# led-array-12x12.net
KiCad netlist of a schematic drawn in EAGLE
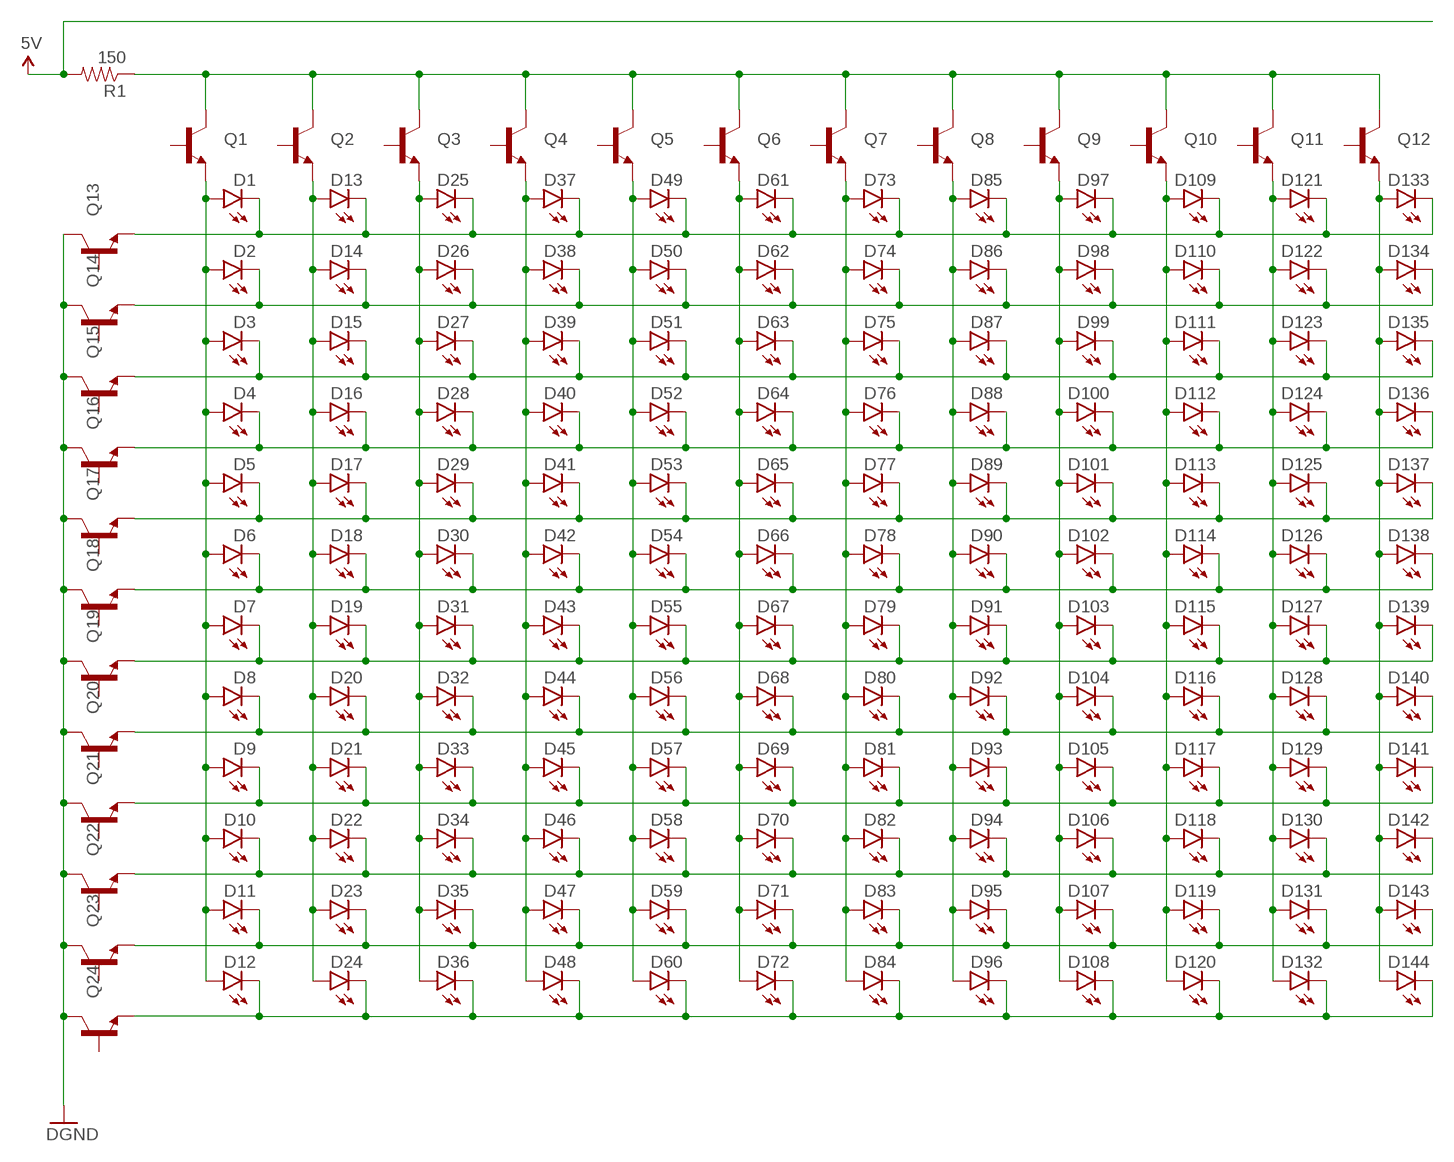
[diagram p0: schematic, sheet 1]

(export (version "E")
  (design (tool "Eeschema 10.0.6"))
  (components
    (comp (ref "D1")
      (value "LED-IR-THRUTSAL6100")
      (footprint "eagle-import:LED5MM")
      (libsource (lib "eagle-import") (part "LED-IR-THRUTSAL6100"))
    )
    (comp (ref "D2")
      (value "LED-IR-THRUTSAL6100")
      (footprint "eagle-import:LED5MM")
      (libsource (lib "eagle-import") (part "LED-IR-THRUTSAL6100"))
    )
    (comp (ref "D3")
      (value "LED-IR-THRUTSAL6100")
      (footprint "eagle-import:LED5MM")
      (libsource (lib "eagle-import") (part "LED-IR-THRUTSAL6100"))
    )
    (comp (ref "D4")
      (value "LED-IR-THRUTSAL6100")
      (footprint "eagle-import:LED5MM")
      (libsource (lib "eagle-import") (part "LED-IR-THRUTSAL6100"))
    )
    (comp (ref "D5")
      (value "LED-IR-THRUTSAL6100")
      (footprint "eagle-import:LED5MM")
      (libsource (lib "eagle-import") (part "LED-IR-THRUTSAL6100"))
    )
    (comp (ref "D6")
      (value "LED-IR-THRUTSAL6100")
      (footprint "eagle-import:LED5MM")
      (libsource (lib "eagle-import") (part "LED-IR-THRUTSAL6100"))
    )
    (comp (ref "D7")
      (value "LED-IR-THRUTSAL6100")
      (footprint "eagle-import:LED5MM")
      (libsource (lib "eagle-import") (part "LED-IR-THRUTSAL6100"))
    )
    (comp (ref "D8")
      (value "LED-IR-THRUTSAL6100")
      (footprint "eagle-import:LED5MM")
      (libsource (lib "eagle-import") (part "LED-IR-THRUTSAL6100"))
    )
    (comp (ref "D9")
      (value "LED-IR-THRUTSAL6100")
      (footprint "eagle-import:LED5MM")
      (libsource (lib "eagle-import") (part "LED-IR-THRUTSAL6100"))
    )
    (comp (ref "D10")
      (value "LED-IR-THRUTSAL6100")
      (footprint "eagle-import:LED5MM")
      (libsource (lib "eagle-import") (part "LED-IR-THRUTSAL6100"))
    )
    (comp (ref "D11")
      (value "LED-IR-THRUTSAL6100")
      (footprint "eagle-import:LED5MM")
      (libsource (lib "eagle-import") (part "LED-IR-THRUTSAL6100"))
    )
    (comp (ref "D12")
      (value "LED-IR-THRUTSAL6100")
      (footprint "eagle-import:LED5MM")
      (libsource (lib "eagle-import") (part "LED-IR-THRUTSAL6100"))
    )
    (comp (ref "D13")
      (value "LED-IR-THRUTSAL6100")
      (footprint "eagle-import:LED5MM")
      (libsource (lib "eagle-import") (part "LED-IR-THRUTSAL6100"))
    )
    (comp (ref "D14")
      (value "LED-IR-THRUTSAL6100")
      (footprint "eagle-import:LED5MM")
      (libsource (lib "eagle-import") (part "LED-IR-THRUTSAL6100"))
    )
    (comp (ref "D15")
      (value "LED-IR-THRUTSAL6100")
      (footprint "eagle-import:LED5MM")
      (libsource (lib "eagle-import") (part "LED-IR-THRUTSAL6100"))
    )
    (comp (ref "D16")
      (value "LED-IR-THRUTSAL6100")
      (footprint "eagle-import:LED5MM")
      (libsource (lib "eagle-import") (part "LED-IR-THRUTSAL6100"))
    )
    (comp (ref "D17")
      (value "LED-IR-THRUTSAL6100")
      (footprint "eagle-import:LED5MM")
      (libsource (lib "eagle-import") (part "LED-IR-THRUTSAL6100"))
    )
    (comp (ref "D18")
      (value "LED-IR-THRUTSAL6100")
      (footprint "eagle-import:LED5MM")
      (libsource (lib "eagle-import") (part "LED-IR-THRUTSAL6100"))
    )
    (comp (ref "D19")
      (value "LED-IR-THRUTSAL6100")
      (footprint "eagle-import:LED5MM")
      (libsource (lib "eagle-import") (part "LED-IR-THRUTSAL6100"))
    )
    (comp (ref "D20")
      (value "LED-IR-THRUTSAL6100")
      (footprint "eagle-import:LED5MM")
      (libsource (lib "eagle-import") (part "LED-IR-THRUTSAL6100"))
    )
    (comp (ref "D21")
      (value "LED-IR-THRUTSAL6100")
      (footprint "eagle-import:LED5MM")
      (libsource (lib "eagle-import") (part "LED-IR-THRUTSAL6100"))
    )
    (comp (ref "D22")
      (value "LED-IR-THRUTSAL6100")
      (footprint "eagle-import:LED5MM")
      (libsource (lib "eagle-import") (part "LED-IR-THRUTSAL6100"))
    )
    (comp (ref "D23")
      (value "LED-IR-THRUTSAL6100")
      (footprint "eagle-import:LED5MM")
      (libsource (lib "eagle-import") (part "LED-IR-THRUTSAL6100"))
    )
    (comp (ref "D24")
      (value "LED-IR-THRUTSAL6100")
      (footprint "eagle-import:LED5MM")
      (libsource (lib "eagle-import") (part "LED-IR-THRUTSAL6100"))
    )
    (comp (ref "D25")
      (value "LED-IR-THRUTSAL6100")
      (footprint "eagle-import:LED5MM")
      (libsource (lib "eagle-import") (part "LED-IR-THRUTSAL6100"))
    )
    (comp (ref "D26")
      (value "LED-IR-THRUTSAL6100")
      (footprint "eagle-import:LED5MM")
      (libsource (lib "eagle-import") (part "LED-IR-THRUTSAL6100"))
    )
    (comp (ref "D27")
      (value "LED-IR-THRUTSAL6100")
      (footprint "eagle-import:LED5MM")
      (libsource (lib "eagle-import") (part "LED-IR-THRUTSAL6100"))
    )
    (comp (ref "D28")
      (value "LED-IR-THRUTSAL6100")
      (footprint "eagle-import:LED5MM")
      (libsource (lib "eagle-import") (part "LED-IR-THRUTSAL6100"))
    )
    (comp (ref "D29")
      (value "LED-IR-THRUTSAL6100")
      (footprint "eagle-import:LED5MM")
      (libsource (lib "eagle-import") (part "LED-IR-THRUTSAL6100"))
    )
    (comp (ref "D30")
      (value "LED-IR-THRUTSAL6100")
      (footprint "eagle-import:LED5MM")
      (libsource (lib "eagle-import") (part "LED-IR-THRUTSAL6100"))
    )
    (comp (ref "D31")
      (value "LED-IR-THRUTSAL6100")
      (footprint "eagle-import:LED5MM")
      (libsource (lib "eagle-import") (part "LED-IR-THRUTSAL6100"))
    )
    (comp (ref "D32")
      (value "LED-IR-THRUTSAL6100")
      (footprint "eagle-import:LED5MM")
      (libsource (lib "eagle-import") (part "LED-IR-THRUTSAL6100"))
    )
    (comp (ref "D33")
      (value "LED-IR-THRUTSAL6100")
      (footprint "eagle-import:LED5MM")
      (libsource (lib "eagle-import") (part "LED-IR-THRUTSAL6100"))
    )
    (comp (ref "D34")
      (value "LED-IR-THRUTSAL6100")
      (footprint "eagle-import:LED5MM")
      (libsource (lib "eagle-import") (part "LED-IR-THRUTSAL6100"))
    )
    (comp (ref "D35")
      (value "LED-IR-THRUTSAL6100")
      (footprint "eagle-import:LED5MM")
      (libsource (lib "eagle-import") (part "LED-IR-THRUTSAL6100"))
    )
    (comp (ref "D36")
      (value "LED-IR-THRUTSAL6100")
      (footprint "eagle-import:LED5MM")
      (libsource (lib "eagle-import") (part "LED-IR-THRUTSAL6100"))
    )
    (comp (ref "D37")
      (value "LED-IR-THRUTSAL6100")
      (footprint "eagle-import:LED5MM")
      (libsource (lib "eagle-import") (part "LED-IR-THRUTSAL6100"))
    )
    (comp (ref "D38")
      (value "LED-IR-THRUTSAL6100")
      (footprint "eagle-import:LED5MM")
      (libsource (lib "eagle-import") (part "LED-IR-THRUTSAL6100"))
    )
    (comp (ref "D39")
      (value "LED-IR-THRUTSAL6100")
      (footprint "eagle-import:LED5MM")
      (libsource (lib "eagle-import") (part "LED-IR-THRUTSAL6100"))
    )
    (comp (ref "D40")
      (value "LED-IR-THRUTSAL6100")
      (footprint "eagle-import:LED5MM")
      (libsource (lib "eagle-import") (part "LED-IR-THRUTSAL6100"))
    )
    (comp (ref "D41")
      (value "LED-IR-THRUTSAL6100")
      (footprint "eagle-import:LED5MM")
      (libsource (lib "eagle-import") (part "LED-IR-THRUTSAL6100"))
    )
    (comp (ref "D42")
      (value "LED-IR-THRUTSAL6100")
      (footprint "eagle-import:LED5MM")
      (libsource (lib "eagle-import") (part "LED-IR-THRUTSAL6100"))
    )
    (comp (ref "D43")
      (value "LED-IR-THRUTSAL6100")
      (footprint "eagle-import:LED5MM")
      (libsource (lib "eagle-import") (part "LED-IR-THRUTSAL6100"))
    )
    (comp (ref "D44")
      (value "LED-IR-THRUTSAL6100")
      (footprint "eagle-import:LED5MM")
      (libsource (lib "eagle-import") (part "LED-IR-THRUTSAL6100"))
    )
    (comp (ref "D45")
      (value "LED-IR-THRUTSAL6100")
      (footprint "eagle-import:LED5MM")
      (libsource (lib "eagle-import") (part "LED-IR-THRUTSAL6100"))
    )
    (comp (ref "D46")
      (value "LED-IR-THRUTSAL6100")
      (footprint "eagle-import:LED5MM")
      (libsource (lib "eagle-import") (part "LED-IR-THRUTSAL6100"))
    )
    (comp (ref "D47")
      (value "LED-IR-THRUTSAL6100")
      (footprint "eagle-import:LED5MM")
      (libsource (lib "eagle-import") (part "LED-IR-THRUTSAL6100"))
    )
    (comp (ref "D48")
      (value "LED-IR-THRUTSAL6100")
      (footprint "eagle-import:LED5MM")
      (libsource (lib "eagle-import") (part "LED-IR-THRUTSAL6100"))
    )
    (comp (ref "D49")
      (value "LED-IR-THRUTSAL6100")
      (footprint "eagle-import:LED5MM")
      (libsource (lib "eagle-import") (part "LED-IR-THRUTSAL6100"))
    )
    (comp (ref "D50")
      (value "LED-IR-THRUTSAL6100")
      (footprint "eagle-import:LED5MM")
      (libsource (lib "eagle-import") (part "LED-IR-THRUTSAL6100"))
    )
    (comp (ref "D51")
      (value "LED-IR-THRUTSAL6100")
      (footprint "eagle-import:LED5MM")
      (libsource (lib "eagle-import") (part "LED-IR-THRUTSAL6100"))
    )
    (comp (ref "D52")
      (value "LED-IR-THRUTSAL6100")
      (footprint "eagle-import:LED5MM")
      (libsource (lib "eagle-import") (part "LED-IR-THRUTSAL6100"))
    )
    (comp (ref "D53")
      (value "LED-IR-THRUTSAL6100")
      (footprint "eagle-import:LED5MM")
      (libsource (lib "eagle-import") (part "LED-IR-THRUTSAL6100"))
    )
    (comp (ref "D54")
      (value "LED-IR-THRUTSAL6100")
      (footprint "eagle-import:LED5MM")
      (libsource (lib "eagle-import") (part "LED-IR-THRUTSAL6100"))
    )
    (comp (ref "D55")
      (value "LED-IR-THRUTSAL6100")
      (footprint "eagle-import:LED5MM")
      (libsource (lib "eagle-import") (part "LED-IR-THRUTSAL6100"))
    )
    (comp (ref "D56")
      (value "LED-IR-THRUTSAL6100")
      (footprint "eagle-import:LED5MM")
      (libsource (lib "eagle-import") (part "LED-IR-THRUTSAL6100"))
    )
    (comp (ref "D57")
      (value "LED-IR-THRUTSAL6100")
      (footprint "eagle-import:LED5MM")
      (libsource (lib "eagle-import") (part "LED-IR-THRUTSAL6100"))
    )
    (comp (ref "D58")
      (value "LED-IR-THRUTSAL6100")
      (footprint "eagle-import:LED5MM")
      (libsource (lib "eagle-import") (part "LED-IR-THRUTSAL6100"))
    )
    (comp (ref "D59")
      (value "LED-IR-THRUTSAL6100")
      (footprint "eagle-import:LED5MM")
      (libsource (lib "eagle-import") (part "LED-IR-THRUTSAL6100"))
    )
    (comp (ref "D60")
      (value "LED-IR-THRUTSAL6100")
      (footprint "eagle-import:LED5MM")
      (libsource (lib "eagle-import") (part "LED-IR-THRUTSAL6100"))
    )
    (comp (ref "D61")
      (value "LED-IR-THRUTSAL6100")
      (footprint "eagle-import:LED5MM")
      (libsource (lib "eagle-import") (part "LED-IR-THRUTSAL6100"))
    )
    (comp (ref "D62")
      (value "LED-IR-THRUTSAL6100")
      (footprint "eagle-import:LED5MM")
      (libsource (lib "eagle-import") (part "LED-IR-THRUTSAL6100"))
    )
    (comp (ref "D63")
      (value "LED-IR-THRUTSAL6100")
      (footprint "eagle-import:LED5MM")
      (libsource (lib "eagle-import") (part "LED-IR-THRUTSAL6100"))
    )
    (comp (ref "D64")
      (value "LED-IR-THRUTSAL6100")
      (footprint "eagle-import:LED5MM")
      (libsource (lib "eagle-import") (part "LED-IR-THRUTSAL6100"))
    )
    (comp (ref "D65")
      (value "LED-IR-THRUTSAL6100")
      (footprint "eagle-import:LED5MM")
      (libsource (lib "eagle-import") (part "LED-IR-THRUTSAL6100"))
    )
    (comp (ref "D66")
      (value "LED-IR-THRUTSAL6100")
      (footprint "eagle-import:LED5MM")
      (libsource (lib "eagle-import") (part "LED-IR-THRUTSAL6100"))
    )
    (comp (ref "D67")
      (value "LED-IR-THRUTSAL6100")
      (footprint "eagle-import:LED5MM")
      (libsource (lib "eagle-import") (part "LED-IR-THRUTSAL6100"))
    )
    (comp (ref "D68")
      (value "LED-IR-THRUTSAL6100")
      (footprint "eagle-import:LED5MM")
      (libsource (lib "eagle-import") (part "LED-IR-THRUTSAL6100"))
    )
    (comp (ref "D69")
      (value "LED-IR-THRUTSAL6100")
      (footprint "eagle-import:LED5MM")
      (libsource (lib "eagle-import") (part "LED-IR-THRUTSAL6100"))
    )
    (comp (ref "D70")
      (value "LED-IR-THRUTSAL6100")
      (footprint "eagle-import:LED5MM")
      (libsource (lib "eagle-import") (part "LED-IR-THRUTSAL6100"))
    )
    (comp (ref "D71")
      (value "LED-IR-THRUTSAL6100")
      (footprint "eagle-import:LED5MM")
      (libsource (lib "eagle-import") (part "LED-IR-THRUTSAL6100"))
    )
    (comp (ref "D72")
      (value "LED-IR-THRUTSAL6100")
      (footprint "eagle-import:LED5MM")
      (libsource (lib "eagle-import") (part "LED-IR-THRUTSAL6100"))
    )
    (comp (ref "D73")
      (value "LED-IR-THRUTSAL6100")
      (footprint "eagle-import:LED5MM")
      (libsource (lib "eagle-import") (part "LED-IR-THRUTSAL6100"))
    )
    (comp (ref "D74")
      (value "LED-IR-THRUTSAL6100")
      (footprint "eagle-import:LED5MM")
      (libsource (lib "eagle-import") (part "LED-IR-THRUTSAL6100"))
    )
    (comp (ref "D75")
      (value "LED-IR-THRUTSAL6100")
      (footprint "eagle-import:LED5MM")
      (libsource (lib "eagle-import") (part "LED-IR-THRUTSAL6100"))
    )
    (comp (ref "D76")
      (value "LED-IR-THRUTSAL6100")
      (footprint "eagle-import:LED5MM")
      (libsource (lib "eagle-import") (part "LED-IR-THRUTSAL6100"))
    )
    (comp (ref "D77")
      (value "LED-IR-THRUTSAL6100")
      (footprint "eagle-import:LED5MM")
      (libsource (lib "eagle-import") (part "LED-IR-THRUTSAL6100"))
    )
    (comp (ref "D78")
      (value "LED-IR-THRUTSAL6100")
      (footprint "eagle-import:LED5MM")
      (libsource (lib "eagle-import") (part "LED-IR-THRUTSAL6100"))
    )
    (comp (ref "D79")
      (value "LED-IR-THRUTSAL6100")
      (footprint "eagle-import:LED5MM")
      (libsource (lib "eagle-import") (part "LED-IR-THRUTSAL6100"))
    )
    (comp (ref "D80")
      (value "LED-IR-THRUTSAL6100")
      (footprint "eagle-import:LED5MM")
      (libsource (lib "eagle-import") (part "LED-IR-THRUTSAL6100"))
    )
    (comp (ref "D81")
      (value "LED-IR-THRUTSAL6100")
      (footprint "eagle-import:LED5MM")
      (libsource (lib "eagle-import") (part "LED-IR-THRUTSAL6100"))
    )
    (comp (ref "D82")
      (value "LED-IR-THRUTSAL6100")
      (footprint "eagle-import:LED5MM")
      (libsource (lib "eagle-import") (part "LED-IR-THRUTSAL6100"))
    )
    (comp (ref "D83")
      (value "LED-IR-THRUTSAL6100")
      (footprint "eagle-import:LED5MM")
      (libsource (lib "eagle-import") (part "LED-IR-THRUTSAL6100"))
    )
    (comp (ref "D84")
      (value "LED-IR-THRUTSAL6100")
      (footprint "eagle-import:LED5MM")
      (libsource (lib "eagle-import") (part "LED-IR-THRUTSAL6100"))
    )
    (comp (ref "D85")
      (value "LED-IR-THRUTSAL6100")
      (footprint "eagle-import:LED5MM")
      (libsource (lib "eagle-import") (part "LED-IR-THRUTSAL6100"))
    )
    (comp (ref "D86")
      (value "LED-IR-THRUTSAL6100")
      (footprint "eagle-import:LED5MM")
      (libsource (lib "eagle-import") (part "LED-IR-THRUTSAL6100"))
    )
    (comp (ref "D87")
      (value "LED-IR-THRUTSAL6100")
      (footprint "eagle-import:LED5MM")
      (libsource (lib "eagle-import") (part "LED-IR-THRUTSAL6100"))
    )
    (comp (ref "D88")
      (value "LED-IR-THRUTSAL6100")
      (footprint "eagle-import:LED5MM")
      (libsource (lib "eagle-import") (part "LED-IR-THRUTSAL6100"))
    )
    (comp (ref "D89")
      (value "LED-IR-THRUTSAL6100")
      (footprint "eagle-import:LED5MM")
      (libsource (lib "eagle-import") (part "LED-IR-THRUTSAL6100"))
    )
    (comp (ref "D90")
      (value "LED-IR-THRUTSAL6100")
      (footprint "eagle-import:LED5MM")
      (libsource (lib "eagle-import") (part "LED-IR-THRUTSAL6100"))
    )
    (comp (ref "D91")
      (value "LED-IR-THRUTSAL6100")
      (footprint "eagle-import:LED5MM")
      (libsource (lib "eagle-import") (part "LED-IR-THRUTSAL6100"))
    )
    (comp (ref "D92")
      (value "LED-IR-THRUTSAL6100")
      (footprint "eagle-import:LED5MM")
      (libsource (lib "eagle-import") (part "LED-IR-THRUTSAL6100"))
    )
    (comp (ref "D93")
      (value "LED-IR-THRUTSAL6100")
      (footprint "eagle-import:LED5MM")
      (libsource (lib "eagle-import") (part "LED-IR-THRUTSAL6100"))
    )
    (comp (ref "D94")
      (value "LED-IR-THRUTSAL6100")
      (footprint "eagle-import:LED5MM")
      (libsource (lib "eagle-import") (part "LED-IR-THRUTSAL6100"))
    )
    (comp (ref "D95")
      (value "LED-IR-THRUTSAL6100")
      (footprint "eagle-import:LED5MM")
      (libsource (lib "eagle-import") (part "LED-IR-THRUTSAL6100"))
    )
    (comp (ref "D96")
      (value "LED-IR-THRUTSAL6100")
      (footprint "eagle-import:LED5MM")
      (libsource (lib "eagle-import") (part "LED-IR-THRUTSAL6100"))
    )
    (comp (ref "D97")
      (value "LED-IR-THRUTSAL6100")
      (footprint "eagle-import:LED5MM")
      (libsource (lib "eagle-import") (part "LED-IR-THRUTSAL6100"))
    )
    (comp (ref "D98")
      (value "LED-IR-THRUTSAL6100")
      (footprint "eagle-import:LED5MM")
      (libsource (lib "eagle-import") (part "LED-IR-THRUTSAL6100"))
    )
    (comp (ref "D99")
      (value "LED-IR-THRUTSAL6100")
      (footprint "eagle-import:LED5MM")
      (libsource (lib "eagle-import") (part "LED-IR-THRUTSAL6100"))
    )
    (comp (ref "D100")
      (value "LED-IR-THRUTSAL6100")
      (footprint "eagle-import:LED5MM")
      (libsource (lib "eagle-import") (part "LED-IR-THRUTSAL6100"))
    )
    (comp (ref "D101")
      (value "LED-IR-THRUTSAL6100")
      (footprint "eagle-import:LED5MM")
      (libsource (lib "eagle-import") (part "LED-IR-THRUTSAL6100"))
    )
    (comp (ref "D102")
      (value "LED-IR-THRUTSAL6100")
      (footprint "eagle-import:LED5MM")
      (libsource (lib "eagle-import") (part "LED-IR-THRUTSAL6100"))
    )
    (comp (ref "D103")
      (value "LED-IR-THRUTSAL6100")
      (footprint "eagle-import:LED5MM")
      (libsource (lib "eagle-import") (part "LED-IR-THRUTSAL6100"))
    )
    (comp (ref "D104")
      (value "LED-IR-THRUTSAL6100")
      (footprint "eagle-import:LED5MM")
      (libsource (lib "eagle-import") (part "LED-IR-THRUTSAL6100"))
    )
    (comp (ref "D105")
      (value "LED-IR-THRUTSAL6100")
      (footprint "eagle-import:LED5MM")
      (libsource (lib "eagle-import") (part "LED-IR-THRUTSAL6100"))
    )
    (comp (ref "D106")
      (value "LED-IR-THRUTSAL6100")
      (footprint "eagle-import:LED5MM")
      (libsource (lib "eagle-import") (part "LED-IR-THRUTSAL6100"))
    )
    (comp (ref "D107")
      (value "LED-IR-THRUTSAL6100")
      (footprint "eagle-import:LED5MM")
      (libsource (lib "eagle-import") (part "LED-IR-THRUTSAL6100"))
    )
    (comp (ref "D108")
      (value "LED-IR-THRUTSAL6100")
      (footprint "eagle-import:LED5MM")
      (libsource (lib "eagle-import") (part "LED-IR-THRUTSAL6100"))
    )
    (comp (ref "D109")
      (value "LED-IR-THRUTSAL6100")
      (footprint "eagle-import:LED5MM")
      (libsource (lib "eagle-import") (part "LED-IR-THRUTSAL6100"))
    )
    (comp (ref "D110")
      (value "LED-IR-THRUTSAL6100")
      (footprint "eagle-import:LED5MM")
      (libsource (lib "eagle-import") (part "LED-IR-THRUTSAL6100"))
    )
    (comp (ref "D111")
      (value "LED-IR-THRUTSAL6100")
      (footprint "eagle-import:LED5MM")
      (libsource (lib "eagle-import") (part "LED-IR-THRUTSAL6100"))
    )
    (comp (ref "D112")
      (value "LED-IR-THRUTSAL6100")
      (footprint "eagle-import:LED5MM")
      (libsource (lib "eagle-import") (part "LED-IR-THRUTSAL6100"))
    )
    (comp (ref "D113")
      (value "LED-IR-THRUTSAL6100")
      (footprint "eagle-import:LED5MM")
      (libsource (lib "eagle-import") (part "LED-IR-THRUTSAL6100"))
    )
    (comp (ref "D114")
      (value "LED-IR-THRUTSAL6100")
      (footprint "eagle-import:LED5MM")
      (libsource (lib "eagle-import") (part "LED-IR-THRUTSAL6100"))
    )
    (comp (ref "D115")
      (value "LED-IR-THRUTSAL6100")
      (footprint "eagle-import:LED5MM")
      (libsource (lib "eagle-import") (part "LED-IR-THRUTSAL6100"))
    )
    (comp (ref "D116")
      (value "LED-IR-THRUTSAL6100")
      (footprint "eagle-import:LED5MM")
      (libsource (lib "eagle-import") (part "LED-IR-THRUTSAL6100"))
    )
    (comp (ref "D117")
      (value "LED-IR-THRUTSAL6100")
      (footprint "eagle-import:LED5MM")
      (libsource (lib "eagle-import") (part "LED-IR-THRUTSAL6100"))
    )
    (comp (ref "D118")
      (value "LED-IR-THRUTSAL6100")
      (footprint "eagle-import:LED5MM")
      (libsource (lib "eagle-import") (part "LED-IR-THRUTSAL6100"))
    )
    (comp (ref "D119")
      (value "LED-IR-THRUTSAL6100")
      (footprint "eagle-import:LED5MM")
      (libsource (lib "eagle-import") (part "LED-IR-THRUTSAL6100"))
    )
    (comp (ref "D120")
      (value "LED-IR-THRUTSAL6100")
      (footprint "eagle-import:LED5MM")
      (libsource (lib "eagle-import") (part "LED-IR-THRUTSAL6100"))
    )
    (comp (ref "D121")
      (value "LED-IR-THRUTSAL6100")
      (footprint "eagle-import:LED5MM")
      (libsource (lib "eagle-import") (part "LED-IR-THRUTSAL6100"))
    )
    (comp (ref "D122")
      (value "LED-IR-THRUTSAL6100")
      (footprint "eagle-import:LED5MM")
      (libsource (lib "eagle-import") (part "LED-IR-THRUTSAL6100"))
    )
    (comp (ref "D123")
      (value "LED-IR-THRUTSAL6100")
      (footprint "eagle-import:LED5MM")
      (libsource (lib "eagle-import") (part "LED-IR-THRUTSAL6100"))
    )
    (comp (ref "D124")
      (value "LED-IR-THRUTSAL6100")
      (footprint "eagle-import:LED5MM")
      (libsource (lib "eagle-import") (part "LED-IR-THRUTSAL6100"))
    )
    (comp (ref "D125")
      (value "LED-IR-THRUTSAL6100")
      (footprint "eagle-import:LED5MM")
      (libsource (lib "eagle-import") (part "LED-IR-THRUTSAL6100"))
    )
    (comp (ref "D126")
      (value "LED-IR-THRUTSAL6100")
      (footprint "eagle-import:LED5MM")
      (libsource (lib "eagle-import") (part "LED-IR-THRUTSAL6100"))
    )
    (comp (ref "D127")
      (value "LED-IR-THRUTSAL6100")
      (footprint "eagle-import:LED5MM")
      (libsource (lib "eagle-import") (part "LED-IR-THRUTSAL6100"))
    )
    (comp (ref "D128")
      (value "LED-IR-THRUTSAL6100")
      (footprint "eagle-import:LED5MM")
      (libsource (lib "eagle-import") (part "LED-IR-THRUTSAL6100"))
    )
    (comp (ref "D129")
      (value "LED-IR-THRUTSAL6100")
      (footprint "eagle-import:LED5MM")
      (libsource (lib "eagle-import") (part "LED-IR-THRUTSAL6100"))
    )
    (comp (ref "D130")
      (value "LED-IR-THRUTSAL6100")
      (footprint "eagle-import:LED5MM")
      (libsource (lib "eagle-import") (part "LED-IR-THRUTSAL6100"))
    )
    (comp (ref "D131")
      (value "LED-IR-THRUTSAL6100")
      (footprint "eagle-import:LED5MM")
      (libsource (lib "eagle-import") (part "LED-IR-THRUTSAL6100"))
    )
    (comp (ref "D132")
      (value "LED-IR-THRUTSAL6100")
      (footprint "eagle-import:LED5MM")
      (libsource (lib "eagle-import") (part "LED-IR-THRUTSAL6100"))
    )
    (comp (ref "D133")
      (value "LED-IR-THRUTSAL6100")
      (footprint "eagle-import:LED5MM")
      (libsource (lib "eagle-import") (part "LED-IR-THRUTSAL6100"))
    )
    (comp (ref "D134")
      (value "LED-IR-THRUTSAL6100")
      (footprint "eagle-import:LED5MM")
      (libsource (lib "eagle-import") (part "LED-IR-THRUTSAL6100"))
    )
    (comp (ref "D135")
      (value "LED-IR-THRUTSAL6100")
      (footprint "eagle-import:LED5MM")
      (libsource (lib "eagle-import") (part "LED-IR-THRUTSAL6100"))
    )
    (comp (ref "D136")
      (value "LED-IR-THRUTSAL6100")
      (footprint "eagle-import:LED5MM")
      (libsource (lib "eagle-import") (part "LED-IR-THRUTSAL6100"))
    )
    (comp (ref "D137")
      (value "LED-IR-THRUTSAL6100")
      (footprint "eagle-import:LED5MM")
      (libsource (lib "eagle-import") (part "LED-IR-THRUTSAL6100"))
    )
    (comp (ref "D138")
      (value "LED-IR-THRUTSAL6100")
      (footprint "eagle-import:LED5MM")
      (libsource (lib "eagle-import") (part "LED-IR-THRUTSAL6100"))
    )
    (comp (ref "D139")
      (value "LED-IR-THRUTSAL6100")
      (footprint "eagle-import:LED5MM")
      (libsource (lib "eagle-import") (part "LED-IR-THRUTSAL6100"))
    )
    (comp (ref "D140")
      (value "LED-IR-THRUTSAL6100")
      (footprint "eagle-import:LED5MM")
      (libsource (lib "eagle-import") (part "LED-IR-THRUTSAL6100"))
    )
    (comp (ref "D141")
      (value "LED-IR-THRUTSAL6100")
      (footprint "eagle-import:LED5MM")
      (libsource (lib "eagle-import") (part "LED-IR-THRUTSAL6100"))
    )
    (comp (ref "D142")
      (value "LED-IR-THRUTSAL6100")
      (footprint "eagle-import:LED5MM")
      (libsource (lib "eagle-import") (part "LED-IR-THRUTSAL6100"))
    )
    (comp (ref "D143")
      (value "LED-IR-THRUTSAL6100")
      (footprint "eagle-import:LED5MM")
      (libsource (lib "eagle-import") (part "LED-IR-THRUTSAL6100"))
    )
    (comp (ref "D144")
      (value "LED-IR-THRUTSAL6100")
      (footprint "eagle-import:LED5MM")
      (libsource (lib "eagle-import") (part "LED-IR-THRUTSAL6100"))
    )
    (comp (ref "Q1")
      (value "TRANSISTOR_NPNMMBT2222A")
      (footprint "eagle-import:SOT23-3")
      (libsource (lib "eagle-import") (part "TRANSISTOR_NPNMMBT2222A"))
    )
    (comp (ref "Q2")
      (value "TRANSISTOR_NPNMMBT2222A")
      (footprint "eagle-import:SOT23-3")
      (libsource (lib "eagle-import") (part "TRANSISTOR_NPNMMBT2222A"))
    )
    (comp (ref "Q3")
      (value "TRANSISTOR_NPNMMBT2222A")
      (footprint "eagle-import:SOT23-3")
      (libsource (lib "eagle-import") (part "TRANSISTOR_NPNMMBT2222A"))
    )
    (comp (ref "Q4")
      (value "TRANSISTOR_NPNMMBT2222A")
      (footprint "eagle-import:SOT23-3")
      (libsource (lib "eagle-import") (part "TRANSISTOR_NPNMMBT2222A"))
    )
    (comp (ref "Q5")
      (value "TRANSISTOR_NPNMMBT2222A")
      (footprint "eagle-import:SOT23-3")
      (libsource (lib "eagle-import") (part "TRANSISTOR_NPNMMBT2222A"))
    )
    (comp (ref "Q6")
      (value "TRANSISTOR_NPNMMBT2222A")
      (footprint "eagle-import:SOT23-3")
      (libsource (lib "eagle-import") (part "TRANSISTOR_NPNMMBT2222A"))
    )
    (comp (ref "Q7")
      (value "TRANSISTOR_NPNMMBT2222A")
      (footprint "eagle-import:SOT23-3")
      (libsource (lib "eagle-import") (part "TRANSISTOR_NPNMMBT2222A"))
    )
    (comp (ref "Q8")
      (value "TRANSISTOR_NPNMMBT2222A")
      (footprint "eagle-import:SOT23-3")
      (libsource (lib "eagle-import") (part "TRANSISTOR_NPNMMBT2222A"))
    )
    (comp (ref "Q9")
      (value "TRANSISTOR_NPNMMBT2222A")
      (footprint "eagle-import:SOT23-3")
      (libsource (lib "eagle-import") (part "TRANSISTOR_NPNMMBT2222A"))
    )
    (comp (ref "Q10")
      (value "TRANSISTOR_NPNMMBT2222A")
      (footprint "eagle-import:SOT23-3")
      (libsource (lib "eagle-import") (part "TRANSISTOR_NPNMMBT2222A"))
    )
    (comp (ref "Q11")
      (value "TRANSISTOR_NPNMMBT2222A")
      (footprint "eagle-import:SOT23-3")
      (libsource (lib "eagle-import") (part "TRANSISTOR_NPNMMBT2222A"))
    )
    (comp (ref "Q12")
      (value "TRANSISTOR_NPNMMBT2222A")
      (footprint "eagle-import:SOT23-3")
      (libsource (lib "eagle-import") (part "TRANSISTOR_NPNMMBT2222A"))
    )
    (comp (ref "Q13")
      (value "TRANSISTOR_NPNMMBT2222A")
      (footprint "eagle-import:SOT23-3")
      (libsource (lib "eagle-import") (part "TRANSISTOR_NPNMMBT2222A"))
    )
    (comp (ref "Q14")
      (value "TRANSISTOR_NPNMMBT2222A")
      (footprint "eagle-import:SOT23-3")
      (libsource (lib "eagle-import") (part "TRANSISTOR_NPNMMBT2222A"))
    )
    (comp (ref "Q15")
      (value "TRANSISTOR_NPNMMBT2222A")
      (footprint "eagle-import:SOT23-3")
      (libsource (lib "eagle-import") (part "TRANSISTOR_NPNMMBT2222A"))
    )
    (comp (ref "Q16")
      (value "TRANSISTOR_NPNMMBT2222A")
      (footprint "eagle-import:SOT23-3")
      (libsource (lib "eagle-import") (part "TRANSISTOR_NPNMMBT2222A"))
    )
    (comp (ref "Q17")
      (value "TRANSISTOR_NPNMMBT2222A")
      (footprint "eagle-import:SOT23-3")
      (libsource (lib "eagle-import") (part "TRANSISTOR_NPNMMBT2222A"))
    )
    (comp (ref "Q18")
      (value "TRANSISTOR_NPNMMBT2222A")
      (footprint "eagle-import:SOT23-3")
      (libsource (lib "eagle-import") (part "TRANSISTOR_NPNMMBT2222A"))
    )
    (comp (ref "Q19")
      (value "TRANSISTOR_NPNMMBT2222A")
      (footprint "eagle-import:SOT23-3")
      (libsource (lib "eagle-import") (part "TRANSISTOR_NPNMMBT2222A"))
    )
    (comp (ref "Q20")
      (value "TRANSISTOR_NPNMMBT2222A")
      (footprint "eagle-import:SOT23-3")
      (libsource (lib "eagle-import") (part "TRANSISTOR_NPNMMBT2222A"))
    )
    (comp (ref "Q21")
      (value "TRANSISTOR_NPNMMBT2222A")
      (footprint "eagle-import:SOT23-3")
      (libsource (lib "eagle-import") (part "TRANSISTOR_NPNMMBT2222A"))
    )
    (comp (ref "Q22")
      (value "TRANSISTOR_NPNMMBT2222A")
      (footprint "eagle-import:SOT23-3")
      (libsource (lib "eagle-import") (part "TRANSISTOR_NPNMMBT2222A"))
    )
    (comp (ref "Q23")
      (value "TRANSISTOR_NPNMMBT2222A")
      (footprint "eagle-import:SOT23-3")
      (libsource (lib "eagle-import") (part "TRANSISTOR_NPNMMBT2222A"))
    )
    (comp (ref "Q24")
      (value "TRANSISTOR_NPNMMBT2222A")
      (footprint "eagle-import:SOT23-3")
      (libsource (lib "eagle-import") (part "TRANSISTOR_NPNMMBT2222A"))
    )
    (comp (ref "R1")
      (value "150")
      (footprint "eagle-import:0805")
      (libsource (lib "eagle-import") (part "RESISTOR0805-RES"))
    )
  )
  (nets
    (net (code "1") (name "5V") (class "Default")
      (node (ref "R1") (pin "2") (pinfunction "2_2") (pintype "passive"))
    )
    (net (code "2") (name "DGND") (class "Default")
      (node (ref "Q13") (pin "3") (pinfunction "C_3") (pintype "passive"))
      (node (ref "Q14") (pin "3") (pinfunction "C_3") (pintype "passive"))
      (node (ref "Q15") (pin "3") (pinfunction "C_3") (pintype "passive"))
      (node (ref "Q16") (pin "3") (pinfunction "C_3") (pintype "passive"))
      (node (ref "Q17") (pin "3") (pinfunction "C_3") (pintype "passive"))
      (node (ref "Q18") (pin "3") (pinfunction "C_3") (pintype "passive"))
      (node (ref "Q19") (pin "3") (pinfunction "C_3") (pintype "passive"))
      (node (ref "Q20") (pin "3") (pinfunction "C_3") (pintype "passive"))
      (node (ref "Q21") (pin "3") (pinfunction "C_3") (pintype "passive"))
      (node (ref "Q22") (pin "3") (pinfunction "C_3") (pintype "passive"))
      (node (ref "Q23") (pin "3") (pinfunction "C_3") (pintype "passive"))
      (node (ref "Q24") (pin "3") (pinfunction "C_3") (pintype "passive"))
    )
    (net (code "3") (name "Net-(D1-C)") (class "Default")
      (node (ref "D1") (pin "K") (pinfunction "C_K") (pintype "passive"))
      (node (ref "D109") (pin "K") (pinfunction "C_K") (pintype "passive"))
      (node (ref "D121") (pin "K") (pinfunction "C_K") (pintype "passive"))
      (node (ref "D13") (pin "K") (pinfunction "C_K") (pintype "passive"))
      (node (ref "D133") (pin "K") (pinfunction "C_K") (pintype "passive"))
      (node (ref "D25") (pin "K") (pinfunction "C_K") (pintype "passive"))
      (node (ref "D37") (pin "K") (pinfunction "C_K") (pintype "passive"))
      (node (ref "D49") (pin "K") (pinfunction "C_K") (pintype "passive"))
      (node (ref "D61") (pin "K") (pinfunction "C_K") (pintype "passive"))
      (node (ref "D73") (pin "K") (pinfunction "C_K") (pintype "passive"))
      (node (ref "D85") (pin "K") (pinfunction "C_K") (pintype "passive"))
      (node (ref "D97") (pin "K") (pinfunction "C_K") (pintype "passive"))
      (node (ref "Q13") (pin "2") (pinfunction "E_2") (pintype "passive"))
    )
    (net (code "4") (name "Net-(D10-C)") (class "Default")
      (node (ref "D10") (pin "K") (pinfunction "C_K") (pintype "passive"))
      (node (ref "D106") (pin "K") (pinfunction "C_K") (pintype "passive"))
      (node (ref "D118") (pin "K") (pinfunction "C_K") (pintype "passive"))
      (node (ref "D130") (pin "K") (pinfunction "C_K") (pintype "passive"))
      (node (ref "D142") (pin "K") (pinfunction "C_K") (pintype "passive"))
      (node (ref "D22") (pin "K") (pinfunction "C_K") (pintype "passive"))
      (node (ref "D34") (pin "K") (pinfunction "C_K") (pintype "passive"))
      (node (ref "D46") (pin "K") (pinfunction "C_K") (pintype "passive"))
      (node (ref "D58") (pin "K") (pinfunction "C_K") (pintype "passive"))
      (node (ref "D70") (pin "K") (pinfunction "C_K") (pintype "passive"))
      (node (ref "D82") (pin "K") (pinfunction "C_K") (pintype "passive"))
      (node (ref "D94") (pin "K") (pinfunction "C_K") (pintype "passive"))
      (node (ref "Q22") (pin "2") (pinfunction "E_2") (pintype "passive"))
    )
    (net (code "5") (name "Net-(D100-C)") (class "Default")
      (node (ref "D100") (pin "K") (pinfunction "C_K") (pintype "passive"))
      (node (ref "D112") (pin "K") (pinfunction "C_K") (pintype "passive"))
      (node (ref "D124") (pin "K") (pinfunction "C_K") (pintype "passive"))
      (node (ref "D136") (pin "K") (pinfunction "C_K") (pintype "passive"))
      (node (ref "D16") (pin "K") (pinfunction "C_K") (pintype "passive"))
      (node (ref "D28") (pin "K") (pinfunction "C_K") (pintype "passive"))
      (node (ref "D4") (pin "K") (pinfunction "C_K") (pintype "passive"))
      (node (ref "D40") (pin "K") (pinfunction "C_K") (pintype "passive"))
      (node (ref "D52") (pin "K") (pinfunction "C_K") (pintype "passive"))
      (node (ref "D64") (pin "K") (pinfunction "C_K") (pintype "passive"))
      (node (ref "D76") (pin "K") (pinfunction "C_K") (pintype "passive"))
      (node (ref "D88") (pin "K") (pinfunction "C_K") (pintype "passive"))
      (node (ref "Q16") (pin "2") (pinfunction "E_2") (pintype "passive"))
    )
    (net (code "6") (name "Net-(D101-C)") (class "Default")
      (node (ref "D101") (pin "K") (pinfunction "C_K") (pintype "passive"))
      (node (ref "D113") (pin "K") (pinfunction "C_K") (pintype "passive"))
      (node (ref "D125") (pin "K") (pinfunction "C_K") (pintype "passive"))
      (node (ref "D137") (pin "K") (pinfunction "C_K") (pintype "passive"))
      (node (ref "D17") (pin "K") (pinfunction "C_K") (pintype "passive"))
      (node (ref "D29") (pin "K") (pinfunction "C_K") (pintype "passive"))
      (node (ref "D41") (pin "K") (pinfunction "C_K") (pintype "passive"))
      (node (ref "D5") (pin "K") (pinfunction "C_K") (pintype "passive"))
      (node (ref "D53") (pin "K") (pinfunction "C_K") (pintype "passive"))
      (node (ref "D65") (pin "K") (pinfunction "C_K") (pintype "passive"))
      (node (ref "D77") (pin "K") (pinfunction "C_K") (pintype "passive"))
      (node (ref "D89") (pin "K") (pinfunction "C_K") (pintype "passive"))
      (node (ref "Q17") (pin "2") (pinfunction "E_2") (pintype "passive"))
    )
    (net (code "7") (name "Net-(D102-C)") (class "Default")
      (node (ref "D102") (pin "K") (pinfunction "C_K") (pintype "passive"))
      (node (ref "D114") (pin "K") (pinfunction "C_K") (pintype "passive"))
      (node (ref "D126") (pin "K") (pinfunction "C_K") (pintype "passive"))
      (node (ref "D138") (pin "K") (pinfunction "C_K") (pintype "passive"))
      (node (ref "D18") (pin "K") (pinfunction "C_K") (pintype "passive"))
      (node (ref "D30") (pin "K") (pinfunction "C_K") (pintype "passive"))
      (node (ref "D42") (pin "K") (pinfunction "C_K") (pintype "passive"))
      (node (ref "D54") (pin "K") (pinfunction "C_K") (pintype "passive"))
      (node (ref "D6") (pin "K") (pinfunction "C_K") (pintype "passive"))
      (node (ref "D66") (pin "K") (pinfunction "C_K") (pintype "passive"))
      (node (ref "D78") (pin "K") (pinfunction "C_K") (pintype "passive"))
      (node (ref "D90") (pin "K") (pinfunction "C_K") (pintype "passive"))
      (node (ref "Q18") (pin "2") (pinfunction "E_2") (pintype "passive"))
    )
    (net (code "8") (name "Net-(D103-C)") (class "Default")
      (node (ref "D103") (pin "K") (pinfunction "C_K") (pintype "passive"))
      (node (ref "D115") (pin "K") (pinfunction "C_K") (pintype "passive"))
      (node (ref "D127") (pin "K") (pinfunction "C_K") (pintype "passive"))
      (node (ref "D139") (pin "K") (pinfunction "C_K") (pintype "passive"))
      (node (ref "D19") (pin "K") (pinfunction "C_K") (pintype "passive"))
      (node (ref "D31") (pin "K") (pinfunction "C_K") (pintype "passive"))
      (node (ref "D43") (pin "K") (pinfunction "C_K") (pintype "passive"))
      (node (ref "D55") (pin "K") (pinfunction "C_K") (pintype "passive"))
      (node (ref "D67") (pin "K") (pinfunction "C_K") (pintype "passive"))
      (node (ref "D7") (pin "K") (pinfunction "C_K") (pintype "passive"))
      (node (ref "D79") (pin "K") (pinfunction "C_K") (pintype "passive"))
      (node (ref "D91") (pin "K") (pinfunction "C_K") (pintype "passive"))
      (node (ref "Q19") (pin "2") (pinfunction "E_2") (pintype "passive"))
    )
    (net (code "9") (name "Net-(D104-C)") (class "Default")
      (node (ref "D104") (pin "K") (pinfunction "C_K") (pintype "passive"))
      (node (ref "D116") (pin "K") (pinfunction "C_K") (pintype "passive"))
      (node (ref "D128") (pin "K") (pinfunction "C_K") (pintype "passive"))
      (node (ref "D140") (pin "K") (pinfunction "C_K") (pintype "passive"))
      (node (ref "D20") (pin "K") (pinfunction "C_K") (pintype "passive"))
      (node (ref "D32") (pin "K") (pinfunction "C_K") (pintype "passive"))
      (node (ref "D44") (pin "K") (pinfunction "C_K") (pintype "passive"))
      (node (ref "D56") (pin "K") (pinfunction "C_K") (pintype "passive"))
      (node (ref "D68") (pin "K") (pinfunction "C_K") (pintype "passive"))
      (node (ref "D8") (pin "K") (pinfunction "C_K") (pintype "passive"))
      (node (ref "D80") (pin "K") (pinfunction "C_K") (pintype "passive"))
      (node (ref "D92") (pin "K") (pinfunction "C_K") (pintype "passive"))
      (node (ref "Q20") (pin "2") (pinfunction "E_2") (pintype "passive"))
    )
    (net (code "10") (name "Net-(D105-C)") (class "Default")
      (node (ref "D105") (pin "K") (pinfunction "C_K") (pintype "passive"))
      (node (ref "D117") (pin "K") (pinfunction "C_K") (pintype "passive"))
      (node (ref "D129") (pin "K") (pinfunction "C_K") (pintype "passive"))
      (node (ref "D141") (pin "K") (pinfunction "C_K") (pintype "passive"))
      (node (ref "D21") (pin "K") (pinfunction "C_K") (pintype "passive"))
      (node (ref "D33") (pin "K") (pinfunction "C_K") (pintype "passive"))
      (node (ref "D45") (pin "K") (pinfunction "C_K") (pintype "passive"))
      (node (ref "D57") (pin "K") (pinfunction "C_K") (pintype "passive"))
      (node (ref "D69") (pin "K") (pinfunction "C_K") (pintype "passive"))
      (node (ref "D81") (pin "K") (pinfunction "C_K") (pintype "passive"))
      (node (ref "D9") (pin "K") (pinfunction "C_K") (pintype "passive"))
      (node (ref "D93") (pin "K") (pinfunction "C_K") (pintype "passive"))
      (node (ref "Q21") (pin "2") (pinfunction "E_2") (pintype "passive"))
    )
    (net (code "11") (name "Net-(D107-C)") (class "Default")
      (node (ref "D107") (pin "K") (pinfunction "C_K") (pintype "passive"))
      (node (ref "D11") (pin "K") (pinfunction "C_K") (pintype "passive"))
      (node (ref "D119") (pin "K") (pinfunction "C_K") (pintype "passive"))
      (node (ref "D131") (pin "K") (pinfunction "C_K") (pintype "passive"))
      (node (ref "D143") (pin "K") (pinfunction "C_K") (pintype "passive"))
      (node (ref "D23") (pin "K") (pinfunction "C_K") (pintype "passive"))
      (node (ref "D35") (pin "K") (pinfunction "C_K") (pintype "passive"))
      (node (ref "D47") (pin "K") (pinfunction "C_K") (pintype "passive"))
      (node (ref "D59") (pin "K") (pinfunction "C_K") (pintype "passive"))
      (node (ref "D71") (pin "K") (pinfunction "C_K") (pintype "passive"))
      (node (ref "D83") (pin "K") (pinfunction "C_K") (pintype "passive"))
      (node (ref "D95") (pin "K") (pinfunction "C_K") (pintype "passive"))
      (node (ref "Q23") (pin "2") (pinfunction "E_2") (pintype "passive"))
    )
    (net (code "12") (name "Net-(D108-C)") (class "Default")
      (node (ref "D108") (pin "K") (pinfunction "C_K") (pintype "passive"))
      (node (ref "D12") (pin "K") (pinfunction "C_K") (pintype "passive"))
      (node (ref "D120") (pin "K") (pinfunction "C_K") (pintype "passive"))
      (node (ref "D132") (pin "K") (pinfunction "C_K") (pintype "passive"))
      (node (ref "D144") (pin "K") (pinfunction "C_K") (pintype "passive"))
      (node (ref "D24") (pin "K") (pinfunction "C_K") (pintype "passive"))
      (node (ref "D36") (pin "K") (pinfunction "C_K") (pintype "passive"))
      (node (ref "D48") (pin "K") (pinfunction "C_K") (pintype "passive"))
      (node (ref "D60") (pin "K") (pinfunction "C_K") (pintype "passive"))
      (node (ref "D72") (pin "K") (pinfunction "C_K") (pintype "passive"))
      (node (ref "D84") (pin "K") (pinfunction "C_K") (pintype "passive"))
      (node (ref "D96") (pin "K") (pinfunction "C_K") (pintype "passive"))
      (node (ref "Q24") (pin "2") (pinfunction "E_2") (pintype "passive"))
    )
    (net (code "13") (name "Net-(D110-C)") (class "Default")
      (node (ref "D110") (pin "K") (pinfunction "C_K") (pintype "passive"))
      (node (ref "D122") (pin "K") (pinfunction "C_K") (pintype "passive"))
      (node (ref "D134") (pin "K") (pinfunction "C_K") (pintype "passive"))
      (node (ref "D14") (pin "K") (pinfunction "C_K") (pintype "passive"))
      (node (ref "D2") (pin "K") (pinfunction "C_K") (pintype "passive"))
      (node (ref "D26") (pin "K") (pinfunction "C_K") (pintype "passive"))
      (node (ref "D38") (pin "K") (pinfunction "C_K") (pintype "passive"))
      (node (ref "D50") (pin "K") (pinfunction "C_K") (pintype "passive"))
      (node (ref "D62") (pin "K") (pinfunction "C_K") (pintype "passive"))
      (node (ref "D74") (pin "K") (pinfunction "C_K") (pintype "passive"))
      (node (ref "D86") (pin "K") (pinfunction "C_K") (pintype "passive"))
      (node (ref "D98") (pin "K") (pinfunction "C_K") (pintype "passive"))
      (node (ref "Q14") (pin "2") (pinfunction "E_2") (pintype "passive"))
    )
    (net (code "14") (name "Net-(D111-C)") (class "Default")
      (node (ref "D111") (pin "K") (pinfunction "C_K") (pintype "passive"))
      (node (ref "D123") (pin "K") (pinfunction "C_K") (pintype "passive"))
      (node (ref "D135") (pin "K") (pinfunction "C_K") (pintype "passive"))
      (node (ref "D15") (pin "K") (pinfunction "C_K") (pintype "passive"))
      (node (ref "D27") (pin "K") (pinfunction "C_K") (pintype "passive"))
      (node (ref "D3") (pin "K") (pinfunction "C_K") (pintype "passive"))
      (node (ref "D39") (pin "K") (pinfunction "C_K") (pintype "passive"))
      (node (ref "D51") (pin "K") (pinfunction "C_K") (pintype "passive"))
      (node (ref "D63") (pin "K") (pinfunction "C_K") (pintype "passive"))
      (node (ref "D75") (pin "K") (pinfunction "C_K") (pintype "passive"))
      (node (ref "D87") (pin "K") (pinfunction "C_K") (pintype "passive"))
      (node (ref "D99") (pin "K") (pinfunction "C_K") (pintype "passive"))
      (node (ref "Q15") (pin "2") (pinfunction "E_2") (pintype "passive"))
    )
    (net (code "15") (name "Net-(Q1-C)") (class "Default")
      (node (ref "Q1") (pin "3") (pinfunction "C_3") (pintype "passive"))
      (node (ref "Q10") (pin "3") (pinfunction "C_3") (pintype "passive"))
      (node (ref "Q11") (pin "3") (pinfunction "C_3") (pintype "passive"))
      (node (ref "Q12") (pin "3") (pinfunction "C_3") (pintype "passive"))
      (node (ref "Q2") (pin "3") (pinfunction "C_3") (pintype "passive"))
      (node (ref "Q3") (pin "3") (pinfunction "C_3") (pintype "passive"))
      (node (ref "Q4") (pin "3") (pinfunction "C_3") (pintype "passive"))
      (node (ref "Q5") (pin "3") (pinfunction "C_3") (pintype "passive"))
      (node (ref "Q6") (pin "3") (pinfunction "C_3") (pintype "passive"))
      (node (ref "Q7") (pin "3") (pinfunction "C_3") (pintype "passive"))
      (node (ref "Q8") (pin "3") (pinfunction "C_3") (pintype "passive"))
      (node (ref "Q9") (pin "3") (pinfunction "C_3") (pintype "passive"))
      (node (ref "R1") (pin "1") (pinfunction "1_1") (pintype "passive"))
    )
    (net (code "16") (name "Net-(Q1-E)") (class "Default")
      (node (ref "D1") (pin "A") (pinfunction "A_A") (pintype "passive"))
      (node (ref "D10") (pin "A") (pinfunction "A_A") (pintype "passive"))
      (node (ref "D11") (pin "A") (pinfunction "A_A") (pintype "passive"))
      (node (ref "D12") (pin "A") (pinfunction "A_A") (pintype "passive"))
      (node (ref "D2") (pin "A") (pinfunction "A_A") (pintype "passive"))
      (node (ref "D3") (pin "A") (pinfunction "A_A") (pintype "passive"))
      (node (ref "D4") (pin "A") (pinfunction "A_A") (pintype "passive"))
      (node (ref "D5") (pin "A") (pinfunction "A_A") (pintype "passive"))
      (node (ref "D6") (pin "A") (pinfunction "A_A") (pintype "passive"))
      (node (ref "D7") (pin "A") (pinfunction "A_A") (pintype "passive"))
      (node (ref "D8") (pin "A") (pinfunction "A_A") (pintype "passive"))
      (node (ref "D9") (pin "A") (pinfunction "A_A") (pintype "passive"))
      (node (ref "Q1") (pin "2") (pinfunction "E_2") (pintype "passive"))
    )
    (net (code "17") (name "Net-(Q2-E)") (class "Default")
      (node (ref "D13") (pin "A") (pinfunction "A_A") (pintype "passive"))
      (node (ref "D14") (pin "A") (pinfunction "A_A") (pintype "passive"))
      (node (ref "D15") (pin "A") (pinfunction "A_A") (pintype "passive"))
      (node (ref "D16") (pin "A") (pinfunction "A_A") (pintype "passive"))
      (node (ref "D17") (pin "A") (pinfunction "A_A") (pintype "passive"))
      (node (ref "D18") (pin "A") (pinfunction "A_A") (pintype "passive"))
      (node (ref "D19") (pin "A") (pinfunction "A_A") (pintype "passive"))
      (node (ref "D20") (pin "A") (pinfunction "A_A") (pintype "passive"))
      (node (ref "D21") (pin "A") (pinfunction "A_A") (pintype "passive"))
      (node (ref "D22") (pin "A") (pinfunction "A_A") (pintype "passive"))
      (node (ref "D23") (pin "A") (pinfunction "A_A") (pintype "passive"))
      (node (ref "D24") (pin "A") (pinfunction "A_A") (pintype "passive"))
      (node (ref "Q2") (pin "2") (pinfunction "E_2") (pintype "passive"))
    )
    (net (code "18") (name "Net-(Q3-E)") (class "Default")
      (node (ref "D25") (pin "A") (pinfunction "A_A") (pintype "passive"))
      (node (ref "D26") (pin "A") (pinfunction "A_A") (pintype "passive"))
      (node (ref "D27") (pin "A") (pinfunction "A_A") (pintype "passive"))
      (node (ref "D28") (pin "A") (pinfunction "A_A") (pintype "passive"))
      (node (ref "D29") (pin "A") (pinfunction "A_A") (pintype "passive"))
      (node (ref "D30") (pin "A") (pinfunction "A_A") (pintype "passive"))
      (node (ref "D31") (pin "A") (pinfunction "A_A") (pintype "passive"))
      (node (ref "D32") (pin "A") (pinfunction "A_A") (pintype "passive"))
      (node (ref "D33") (pin "A") (pinfunction "A_A") (pintype "passive"))
      (node (ref "D34") (pin "A") (pinfunction "A_A") (pintype "passive"))
      (node (ref "D35") (pin "A") (pinfunction "A_A") (pintype "passive"))
      (node (ref "D36") (pin "A") (pinfunction "A_A") (pintype "passive"))
      (node (ref "Q3") (pin "2") (pinfunction "E_2") (pintype "passive"))
    )
    (net (code "19") (name "Net-(Q4-E)") (class "Default")
      (node (ref "D37") (pin "A") (pinfunction "A_A") (pintype "passive"))
      (node (ref "D38") (pin "A") (pinfunction "A_A") (pintype "passive"))
      (node (ref "D39") (pin "A") (pinfunction "A_A") (pintype "passive"))
      (node (ref "D40") (pin "A") (pinfunction "A_A") (pintype "passive"))
      (node (ref "D41") (pin "A") (pinfunction "A_A") (pintype "passive"))
      (node (ref "D42") (pin "A") (pinfunction "A_A") (pintype "passive"))
      (node (ref "D43") (pin "A") (pinfunction "A_A") (pintype "passive"))
      (node (ref "D44") (pin "A") (pinfunction "A_A") (pintype "passive"))
      (node (ref "D45") (pin "A") (pinfunction "A_A") (pintype "passive"))
      (node (ref "D46") (pin "A") (pinfunction "A_A") (pintype "passive"))
      (node (ref "D47") (pin "A") (pinfunction "A_A") (pintype "passive"))
      (node (ref "D48") (pin "A") (pinfunction "A_A") (pintype "passive"))
      (node (ref "Q4") (pin "2") (pinfunction "E_2") (pintype "passive"))
    )
    (net (code "20") (name "Net-(Q5-E)") (class "Default")
      (node (ref "D49") (pin "A") (pinfunction "A_A") (pintype "passive"))
      (node (ref "D50") (pin "A") (pinfunction "A_A") (pintype "passive"))
      (node (ref "D51") (pin "A") (pinfunction "A_A") (pintype "passive"))
      (node (ref "D52") (pin "A") (pinfunction "A_A") (pintype "passive"))
      (node (ref "D53") (pin "A") (pinfunction "A_A") (pintype "passive"))
      (node (ref "D54") (pin "A") (pinfunction "A_A") (pintype "passive"))
      (node (ref "D55") (pin "A") (pinfunction "A_A") (pintype "passive"))
      (node (ref "D56") (pin "A") (pinfunction "A_A") (pintype "passive"))
      (node (ref "D57") (pin "A") (pinfunction "A_A") (pintype "passive"))
      (node (ref "D58") (pin "A") (pinfunction "A_A") (pintype "passive"))
      (node (ref "D59") (pin "A") (pinfunction "A_A") (pintype "passive"))
      (node (ref "D60") (pin "A") (pinfunction "A_A") (pintype "passive"))
      (node (ref "Q5") (pin "2") (pinfunction "E_2") (pintype "passive"))
    )
    (net (code "21") (name "Net-(Q6-E)") (class "Default")
      (node (ref "D61") (pin "A") (pinfunction "A_A") (pintype "passive"))
      (node (ref "D62") (pin "A") (pinfunction "A_A") (pintype "passive"))
      (node (ref "D63") (pin "A") (pinfunction "A_A") (pintype "passive"))
      (node (ref "D64") (pin "A") (pinfunction "A_A") (pintype "passive"))
      (node (ref "D65") (pin "A") (pinfunction "A_A") (pintype "passive"))
      (node (ref "D66") (pin "A") (pinfunction "A_A") (pintype "passive"))
      (node (ref "D67") (pin "A") (pinfunction "A_A") (pintype "passive"))
      (node (ref "D68") (pin "A") (pinfunction "A_A") (pintype "passive"))
      (node (ref "D69") (pin "A") (pinfunction "A_A") (pintype "passive"))
      (node (ref "D70") (pin "A") (pinfunction "A_A") (pintype "passive"))
      (node (ref "D71") (pin "A") (pinfunction "A_A") (pintype "passive"))
      (node (ref "D72") (pin "A") (pinfunction "A_A") (pintype "passive"))
      (node (ref "Q6") (pin "2") (pinfunction "E_2") (pintype "passive"))
    )
    (net (code "22") (name "Net-(Q7-E)") (class "Default")
      (node (ref "D73") (pin "A") (pinfunction "A_A") (pintype "passive"))
      (node (ref "D74") (pin "A") (pinfunction "A_A") (pintype "passive"))
      (node (ref "D75") (pin "A") (pinfunction "A_A") (pintype "passive"))
      (node (ref "D76") (pin "A") (pinfunction "A_A") (pintype "passive"))
      (node (ref "D77") (pin "A") (pinfunction "A_A") (pintype "passive"))
      (node (ref "D78") (pin "A") (pinfunction "A_A") (pintype "passive"))
      (node (ref "D79") (pin "A") (pinfunction "A_A") (pintype "passive"))
      (node (ref "D80") (pin "A") (pinfunction "A_A") (pintype "passive"))
      (node (ref "D81") (pin "A") (pinfunction "A_A") (pintype "passive"))
      (node (ref "D82") (pin "A") (pinfunction "A_A") (pintype "passive"))
      (node (ref "D83") (pin "A") (pinfunction "A_A") (pintype "passive"))
      (node (ref "D84") (pin "A") (pinfunction "A_A") (pintype "passive"))
      (node (ref "Q7") (pin "2") (pinfunction "E_2") (pintype "passive"))
    )
    (net (code "23") (name "Net-(Q8-E)") (class "Default")
      (node (ref "D85") (pin "A") (pinfunction "A_A") (pintype "passive"))
      (node (ref "D86") (pin "A") (pinfunction "A_A") (pintype "passive"))
      (node (ref "D87") (pin "A") (pinfunction "A_A") (pintype "passive"))
      (node (ref "D88") (pin "A") (pinfunction "A_A") (pintype "passive"))
      (node (ref "D89") (pin "A") (pinfunction "A_A") (pintype "passive"))
      (node (ref "D90") (pin "A") (pinfunction "A_A") (pintype "passive"))
      (node (ref "D91") (pin "A") (pinfunction "A_A") (pintype "passive"))
      (node (ref "D92") (pin "A") (pinfunction "A_A") (pintype "passive"))
      (node (ref "D93") (pin "A") (pinfunction "A_A") (pintype "passive"))
      (node (ref "D94") (pin "A") (pinfunction "A_A") (pintype "passive"))
      (node (ref "D95") (pin "A") (pinfunction "A_A") (pintype "passive"))
      (node (ref "D96") (pin "A") (pinfunction "A_A") (pintype "passive"))
      (node (ref "Q8") (pin "2") (pinfunction "E_2") (pintype "passive"))
    )
    (net (code "24") (name "Net-(Q9-E)") (class "Default")
      (node (ref "D100") (pin "A") (pinfunction "A_A") (pintype "passive"))
      (node (ref "D101") (pin "A") (pinfunction "A_A") (pintype "passive"))
      (node (ref "D102") (pin "A") (pinfunction "A_A") (pintype "passive"))
      (node (ref "D103") (pin "A") (pinfunction "A_A") (pintype "passive"))
      (node (ref "D104") (pin "A") (pinfunction "A_A") (pintype "passive"))
      (node (ref "D105") (pin "A") (pinfunction "A_A") (pintype "passive"))
      (node (ref "D106") (pin "A") (pinfunction "A_A") (pintype "passive"))
      (node (ref "D107") (pin "A") (pinfunction "A_A") (pintype "passive"))
      (node (ref "D108") (pin "A") (pinfunction "A_A") (pintype "passive"))
      (node (ref "D97") (pin "A") (pinfunction "A_A") (pintype "passive"))
      (node (ref "D98") (pin "A") (pinfunction "A_A") (pintype "passive"))
      (node (ref "D99") (pin "A") (pinfunction "A_A") (pintype "passive"))
      (node (ref "Q9") (pin "2") (pinfunction "E_2") (pintype "passive"))
    )
    (net (code "25") (name "Net-(Q10-E)") (class "Default")
      (node (ref "D109") (pin "A") (pinfunction "A_A") (pintype "passive"))
      (node (ref "D110") (pin "A") (pinfunction "A_A") (pintype "passive"))
      (node (ref "D111") (pin "A") (pinfunction "A_A") (pintype "passive"))
      (node (ref "D112") (pin "A") (pinfunction "A_A") (pintype "passive"))
      (node (ref "D113") (pin "A") (pinfunction "A_A") (pintype "passive"))
      (node (ref "D114") (pin "A") (pinfunction "A_A") (pintype "passive"))
      (node (ref "D115") (pin "A") (pinfunction "A_A") (pintype "passive"))
      (node (ref "D116") (pin "A") (pinfunction "A_A") (pintype "passive"))
      (node (ref "D117") (pin "A") (pinfunction "A_A") (pintype "passive"))
      (node (ref "D118") (pin "A") (pinfunction "A_A") (pintype "passive"))
      (node (ref "D119") (pin "A") (pinfunction "A_A") (pintype "passive"))
      (node (ref "D120") (pin "A") (pinfunction "A_A") (pintype "passive"))
      (node (ref "Q10") (pin "2") (pinfunction "E_2") (pintype "passive"))
    )
    (net (code "26") (name "Net-(Q11-E)") (class "Default")
      (node (ref "D121") (pin "A") (pinfunction "A_A") (pintype "passive"))
      (node (ref "D122") (pin "A") (pinfunction "A_A") (pintype "passive"))
      (node (ref "D123") (pin "A") (pinfunction "A_A") (pintype "passive"))
      (node (ref "D124") (pin "A") (pinfunction "A_A") (pintype "passive"))
      (node (ref "D125") (pin "A") (pinfunction "A_A") (pintype "passive"))
      (node (ref "D126") (pin "A") (pinfunction "A_A") (pintype "passive"))
      (node (ref "D127") (pin "A") (pinfunction "A_A") (pintype "passive"))
      (node (ref "D128") (pin "A") (pinfunction "A_A") (pintype "passive"))
      (node (ref "D129") (pin "A") (pinfunction "A_A") (pintype "passive"))
      (node (ref "D130") (pin "A") (pinfunction "A_A") (pintype "passive"))
      (node (ref "D131") (pin "A") (pinfunction "A_A") (pintype "passive"))
      (node (ref "D132") (pin "A") (pinfunction "A_A") (pintype "passive"))
      (node (ref "Q11") (pin "2") (pinfunction "E_2") (pintype "passive"))
    )
    (net (code "27") (name "Net-(Q12-E)") (class "Default")
      (node (ref "D133") (pin "A") (pinfunction "A_A") (pintype "passive"))
      (node (ref "D134") (pin "A") (pinfunction "A_A") (pintype "passive"))
      (node (ref "D135") (pin "A") (pinfunction "A_A") (pintype "passive"))
      (node (ref "D136") (pin "A") (pinfunction "A_A") (pintype "passive"))
      (node (ref "D137") (pin "A") (pinfunction "A_A") (pintype "passive"))
      (node (ref "D138") (pin "A") (pinfunction "A_A") (pintype "passive"))
      (node (ref "D139") (pin "A") (pinfunction "A_A") (pintype "passive"))
      (node (ref "D140") (pin "A") (pinfunction "A_A") (pintype "passive"))
      (node (ref "D141") (pin "A") (pinfunction "A_A") (pintype "passive"))
      (node (ref "D142") (pin "A") (pinfunction "A_A") (pintype "passive"))
      (node (ref "D143") (pin "A") (pinfunction "A_A") (pintype "passive"))
      (node (ref "D144") (pin "A") (pinfunction "A_A") (pintype "passive"))
      (node (ref "Q12") (pin "2") (pinfunction "E_2") (pintype "passive"))
    )
    (net (code "28") (name "unconnected-(Q1-B-Pad1)") (class "Default")
      (node (ref "Q1") (pin "1") (pinfunction "B_1") (pintype "passive"))
    )
    (net (code "29") (name "unconnected-(Q2-B-Pad1)") (class "Default")
      (node (ref "Q2") (pin "1") (pinfunction "B_1") (pintype "passive"))
    )
    (net (code "30") (name "unconnected-(Q3-B-Pad1)") (class "Default")
      (node (ref "Q3") (pin "1") (pinfunction "B_1") (pintype "passive"))
    )
    (net (code "31") (name "unconnected-(Q4-B-Pad1)") (class "Default")
      (node (ref "Q4") (pin "1") (pinfunction "B_1") (pintype "passive"))
    )
    (net (code "32") (name "unconnected-(Q5-B-Pad1)") (class "Default")
      (node (ref "Q5") (pin "1") (pinfunction "B_1") (pintype "passive"))
    )
    (net (code "33") (name "unconnected-(Q6-B-Pad1)") (class "Default")
      (node (ref "Q6") (pin "1") (pinfunction "B_1") (pintype "passive"))
    )
    (net (code "34") (name "unconnected-(Q7-B-Pad1)") (class "Default")
      (node (ref "Q7") (pin "1") (pinfunction "B_1") (pintype "passive"))
    )
    (net (code "35") (name "unconnected-(Q8-B-Pad1)") (class "Default")
      (node (ref "Q8") (pin "1") (pinfunction "B_1") (pintype "passive"))
    )
    (net (code "36") (name "unconnected-(Q9-B-Pad1)") (class "Default")
      (node (ref "Q9") (pin "1") (pinfunction "B_1") (pintype "passive"))
    )
    (net (code "37") (name "unconnected-(Q10-B-Pad1)") (class "Default")
      (node (ref "Q10") (pin "1") (pinfunction "B_1") (pintype "passive"))
    )
    (net (code "38") (name "unconnected-(Q11-B-Pad1)") (class "Default")
      (node (ref "Q11") (pin "1") (pinfunction "B_1") (pintype "passive"))
    )
    (net (code "39") (name "unconnected-(Q12-B-Pad1)") (class "Default")
      (node (ref "Q12") (pin "1") (pinfunction "B_1") (pintype "passive"))
    )
    (net (code "40") (name "unconnected-(Q13-B-Pad1)") (class "Default")
      (node (ref "Q13") (pin "1") (pinfunction "B_1") (pintype "passive"))
    )
    (net (code "41") (name "unconnected-(Q14-B-Pad1)") (class "Default")
      (node (ref "Q14") (pin "1") (pinfunction "B_1") (pintype "passive"))
    )
    (net (code "42") (name "unconnected-(Q15-B-Pad1)") (class "Default")
      (node (ref "Q15") (pin "1") (pinfunction "B_1") (pintype "passive"))
    )
    (net (code "43") (name "unconnected-(Q16-B-Pad1)") (class "Default")
      (node (ref "Q16") (pin "1") (pinfunction "B_1") (pintype "passive"))
    )
    (net (code "44") (name "unconnected-(Q17-B-Pad1)") (class "Default")
      (node (ref "Q17") (pin "1") (pinfunction "B_1") (pintype "passive"))
    )
    (net (code "45") (name "unconnected-(Q18-B-Pad1)") (class "Default")
      (node (ref "Q18") (pin "1") (pinfunction "B_1") (pintype "passive"))
    )
    (net (code "46") (name "unconnected-(Q19-B-Pad1)") (class "Default")
      (node (ref "Q19") (pin "1") (pinfunction "B_1") (pintype "passive"))
    )
    (net (code "47") (name "unconnected-(Q20-B-Pad1)") (class "Default")
      (node (ref "Q20") (pin "1") (pinfunction "B_1") (pintype "passive"))
    )
    (net (code "48") (name "unconnected-(Q21-B-Pad1)") (class "Default")
      (node (ref "Q21") (pin "1") (pinfunction "B_1") (pintype "passive"))
    )
    (net (code "49") (name "unconnected-(Q22-B-Pad1)") (class "Default")
      (node (ref "Q22") (pin "1") (pinfunction "B_1") (pintype "passive"))
    )
    (net (code "50") (name "unconnected-(Q23-B-Pad1)") (class "Default")
      (node (ref "Q23") (pin "1") (pinfunction "B_1") (pintype "passive"))
    )
    (net (code "51") (name "unconnected-(Q24-B-Pad1)") (class "Default")
      (node (ref "Q24") (pin "1") (pinfunction "B_1") (pintype "passive"))
    )
  )
)
